# sd_debug.net
KiCad netlist of a schematic drawn in Altium Designer
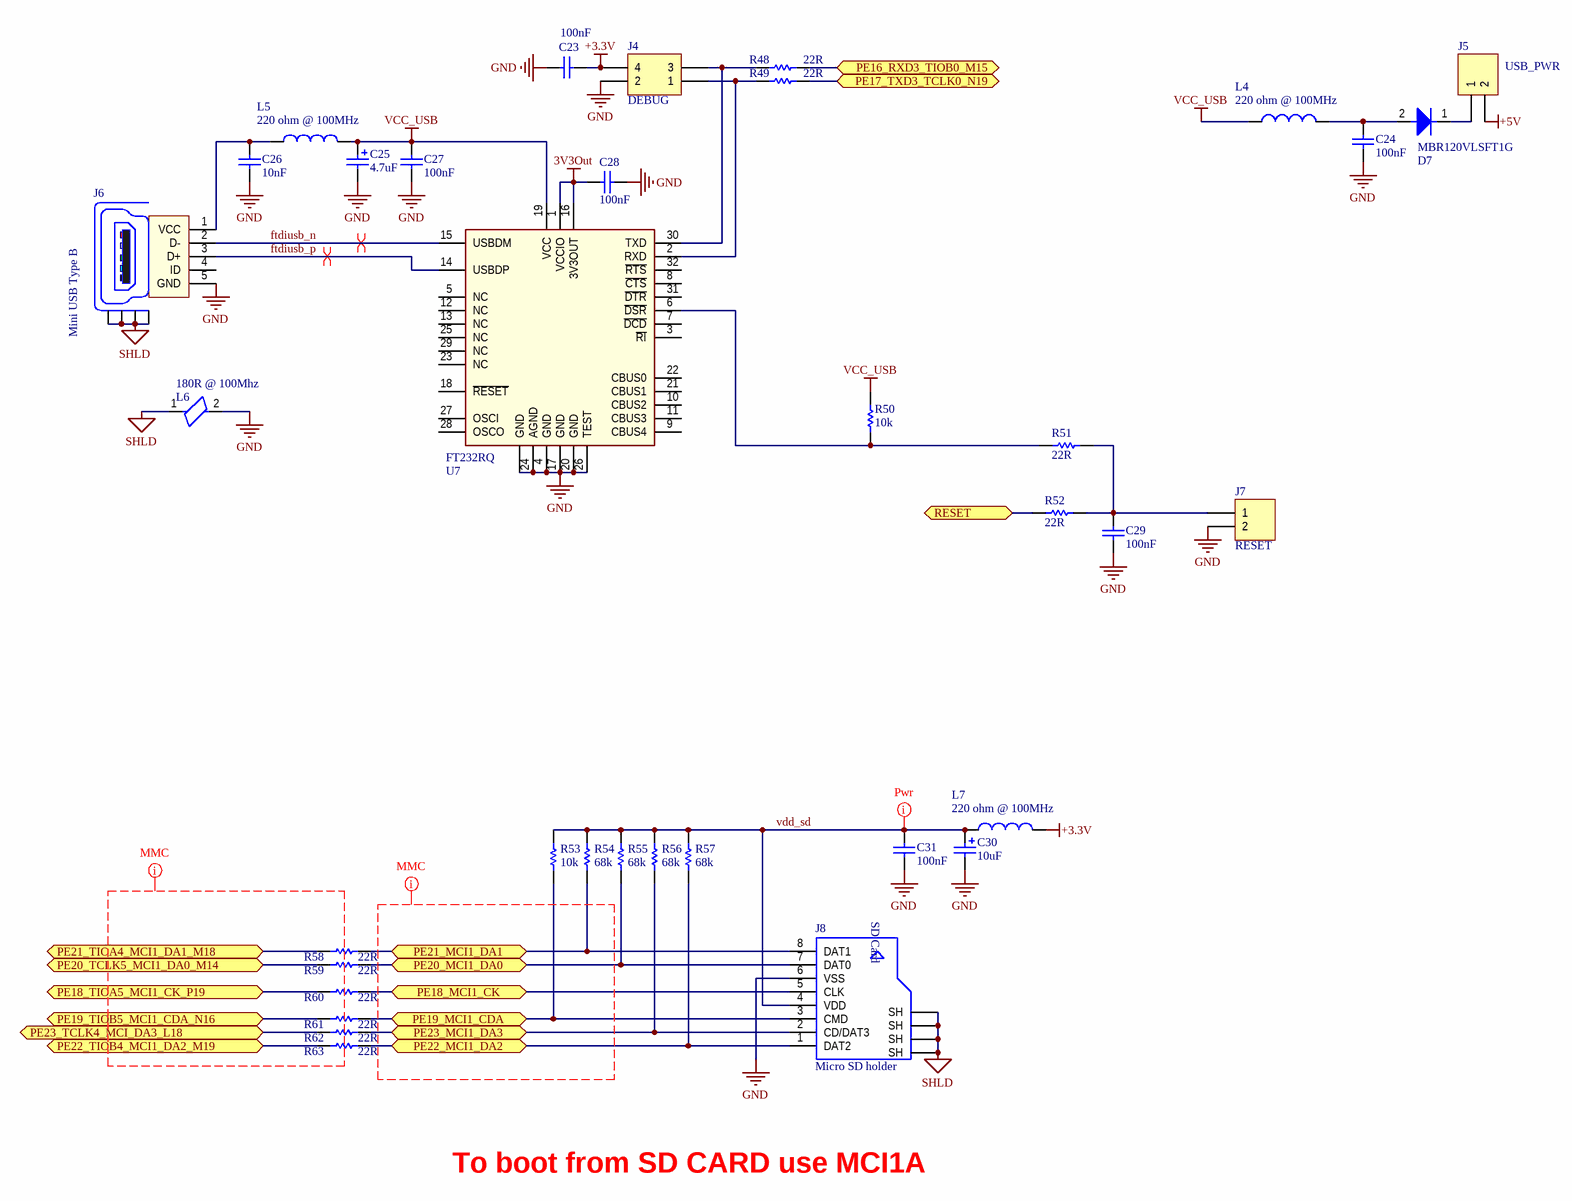
[diagram p0: sd_debug.SchDoc]

(export (version "E")
  (design (tool "Eeschema 10.0.6"))
  (components
    (comp (ref "C23")
      (value "100nF")
      (footprint "0603_[1608]")
      (description "Ceramic X7R 50V")
      (fields (field (name "PUBLISHER") "Altium Limited"))
      (libsource (lib "DEVELER_Library") (part "Cap"))
    )
    (comp (ref "C24")
      (value "100nF")
      (footprint "0603_[1608]")
      (description "Ceramic X7R 50V")
      (fields (field (name "PUBLISHER") "Altium Limited"))
      (libsource (lib "DEVELER_Library") (part "Cap"))
    )
    (comp (ref "C25")
      (value "4.7uF")
      (footprint "1206_[3216]")
      (description "Ceramic X5R 25V")
      (fields (field (name "PUBLISHER") "Altium Limited"))
      (libsource (lib "DEVELER_Library") (part "Cap Pol1"))
    )
    (comp (ref "C26")
      (value "10nF")
      (footprint "0603_[1608]")
      (description "Ceramic X7R 50V")
      (fields (field (name "PUBLISHER") "Altium Limited"))
      (libsource (lib "DEVELER_Library") (part "Cap"))
    )
    (comp (ref "C27")
      (value "100nF")
      (footprint "0603_[1608]")
      (description "Ceramic X7R 50V")
      (fields (field (name "PUBLISHER") "Altium Limited"))
      (libsource (lib "DEVELER_Library") (part "Cap"))
    )
    (comp (ref "C28")
      (value "100nF")
      (footprint "0603_[1608]")
      (description "Ceramic X7R 50V")
      (fields (field (name "PUBLISHER") "Altium Limited"))
      (libsource (lib "DEVELER_Library") (part "Cap"))
    )
    (comp (ref "C29")
      (value "100nF")
      (footprint "0603_[1608]")
      (description "Ceramic X7R 50V")
      (fields (field (name "PUBLISHER") "Altium Limited"))
      (libsource (lib "DEVELER_Library") (part "Cap"))
    )
    (comp (ref "C30")
      (value "10uF")
      (footprint "1206_[3216]")
      (description "Ceramic X5R 25V")
      (fields (field (name "PUBLISHER") "Altium Limited"))
      (libsource (lib "DEVELER_Library") (part "Cap Pol1"))
    )
    (comp (ref "C31")
      (value "100nF")
      (footprint "0603_[1608]")
      (description "Ceramic X7R 50V")
      (fields (field (name "PUBLISHER") "Altium Limited"))
      (libsource (lib "Miscellaneous Devices") (part "Cap"))
    )
    (comp (ref "D7")
      (value "MBR120VLSFT1G")
      (footprint "SOD-123")
      (description "Diode Schottky  low Vf, If 1A (PMEG3010ER; MBRX120LF)")
      (libsource (lib "DEVELER_Library") (part "Diode"))
    )
    (comp (ref "J4")
      (value "DEBUG")
      (footprint "HEADER_2X2_2.54MM_THD")
      (description "Pin Header, 4pin, 2x2, 2.54mm, THD")
      (fields (field (name "PUBLISHER") "Altium Limited"))
      (libsource (lib "Miscellaneous Connectors") (part "Header 2X2"))
    )
    (comp (ref "J5")
      (value "USB_PWR")
      (footprint "HEADER_1X2_2.54MM_THD")
      (description "Pin Header, 2pin, 1x2, 2.54mm, THD")
      (fields (field (name "PUBLISHER") "Altium Limited"))
      (libsource (lib "Miscellaneous Connectors") (part "Header 2"))
    )
    (comp (ref "J6")
      (value "Mini USB Type B")
      (footprint "usb_typeB_mini_smd")
      (description "Mini USB SMT Type B 5 Contacts (WE 65100516121)")
      (fields
        (field (name "MANUFACTURER") "Würth Elektronik eiSos GmbH")
        (field (name "PARTNO") "65100516121")
        (field (name "CREATED BY") "Karrer Zheng")
      )
      (libsource (lib "DEVELER_Library") (part "USB_Con_Type_B_mini_SMT"))
    )
    (comp (ref "J7")
      (value "RESET")
      (footprint "HEADER_1X2_2.54MM_THD")
      (description "Pin Header, 2pin, 1x2, 2.54mm, THD")
      (fields (field (name "PUBLISHER") "Altium Limited"))
      (libsource (lib "") (part "Header 2_1"))
    )
    (comp (ref "J8")
      (value "Micro SD holder")
      (footprint "micro_sd_holder_pp")
      (description "WR-CRD Micro SD_Push and Push (693071010811)")
      (fields
        (field (name "MANUFACTURER") "Würth Elektronik eiSos GmbH")
        (field (name "PARTNO") "693071010811")
        (field (name "CREATED BY") "Karrer Zheng")
      )
      (libsource (lib "DEVELER_Library") (part "micro_sd_holde"))
    )
    (comp (ref "L4")
      (value "220 ohm @ 100MHz")
      (footprint "0805_[2012]")
      (description "WE 742792022")
      (libsource (lib "DEVELER_Library") (part "Inductor"))
    )
    (comp (ref "L5")
      (value "220 ohm @ 100MHz")
      (footprint "0805_[2012]")
      (description "WE 742792022")
      (libsource (lib "DEVELER_Library") (part "Inductor"))
    )
    (comp (ref "L6")
      (value "180R @ 100Mhz")
      (footprint "0603_[1608]")
      (description "Ferrite Beat (WE 7427927218)")
      (libsource (lib "project42_lib") (part "BEAD_ FERRITE"))
    )
    (comp (ref "L7")
      (value "220 ohm @ 100MHz")
      (footprint "0805_[2012]")
      (description "WE 742792022")
      (libsource (lib "DEVELER_Library") (part "Inductor"))
    )
    (comp (ref "R48")
      (value "22R")
      (footprint "0603_[1608]")
      (description "Resistor")
      (fields (field (name "PUBLISHER") "Altium Limited"))
      (libsource (lib "DEVELER_Library") (part "Res1"))
    )
    (comp (ref "R49")
      (value "22R")
      (footprint "0603_[1608]")
      (description "Resistor")
      (fields (field (name "PUBLISHER") "Altium Limited"))
      (libsource (lib "DEVELER_Library") (part "Res1"))
    )
    (comp (ref "R50")
      (value "10k")
      (footprint "0603_[1608]")
      (description "Resistor")
      (fields (field (name "PUBLISHER") "Altium Limited"))
      (libsource (lib "DEVELER_Library") (part "Res1"))
    )
    (comp (ref "R51")
      (value "22R")
      (footprint "0603_[1608]")
      (description "Resistor")
      (fields (field (name "PUBLISHER") "Altium Limited"))
      (libsource (lib "DEVELER_Library") (part "Res1"))
    )
    (comp (ref "R52")
      (value "22R")
      (footprint "0603_[1608]")
      (description "Resistor")
      (fields (field (name "PUBLISHER") "Altium Limited"))
      (libsource (lib "DEVELER_Library") (part "Res1"))
    )
    (comp (ref "R53")
      (value "10k")
      (footprint "0603_[1608]")
      (description "Resistor")
      (fields (field (name "PUBLISHER") "Altium Limited"))
      (libsource (lib "DEVELER_Library") (part "Res1"))
    )
    (comp (ref "R54")
      (value "68k")
      (footprint "0603_[1608]")
      (description "Resistor")
      (fields (field (name "PUBLISHER") "Altium Limited"))
      (libsource (lib "DEVELER_Library") (part "Res1"))
    )
    (comp (ref "R55")
      (value "68k")
      (footprint "0603_[1608]")
      (description "Resistor")
      (fields (field (name "PUBLISHER") "Altium Limited"))
      (libsource (lib "DEVELER_Library") (part "Res1"))
    )
    (comp (ref "R56")
      (value "68k")
      (footprint "0603_[1608]")
      (description "Resistor")
      (fields (field (name "PUBLISHER") "Altium Limited"))
      (libsource (lib "DEVELER_Library") (part "Res1"))
    )
    (comp (ref "R57")
      (value "68k")
      (footprint "0603_[1608]")
      (description "Resistor")
      (fields (field (name "PUBLISHER") "Altium Limited"))
      (libsource (lib "DEVELER_Library") (part "Res1"))
    )
    (comp (ref "R58")
      (value "22R")
      (footprint "0603_[1608]")
      (description "Resistor")
      (fields (field (name "PUBLISHER") "Altium Limited"))
      (libsource (lib "DEVELER_Library") (part "Res1"))
    )
    (comp (ref "R59")
      (value "22R")
      (footprint "0603_[1608]")
      (description "Resistor")
      (fields (field (name "PUBLISHER") "Altium Limited"))
      (libsource (lib "DEVELER_Library") (part "Res1"))
    )
    (comp (ref "R60")
      (value "22R")
      (footprint "0603_[1608]")
      (description "Resistor")
      (fields (field (name "PUBLISHER") "Altium Limited"))
      (libsource (lib "DEVELER_Library") (part "Res1"))
    )
    (comp (ref "R61")
      (value "22R")
      (footprint "0603_[1608]")
      (description "Resistor")
      (fields (field (name "PUBLISHER") "Altium Limited"))
      (libsource (lib "DEVELER_Library") (part "Res1"))
    )
    (comp (ref "R62")
      (value "22R")
      (footprint "0603_[1608]")
      (description "Resistor")
      (fields (field (name "PUBLISHER") "Altium Limited"))
      (libsource (lib "DEVELER_Library") (part "Res1"))
    )
    (comp (ref "R63")
      (value "22R")
      (footprint "0603_[1608]")
      (description "Resistor")
      (fields (field (name "PUBLISHER") "Altium Limited"))
      (libsource (lib "DEVELER_Library") (part "Res1"))
    )
    (comp (ref "U7")
      (value "FT232RQ")
      (footprint "QFN-32")
      (description "Serial TTL 232 <-> USB (QFN-32)")
      (libsource (lib "DEVELER_Library") (part "FT232RQ"))
    )
  )
  (nets
    (net (code "1") (name "+3.3V") (class "Default")
      (node (ref "C23") (pin "1") (pinfunction "1_1") (pintype "passive"))
      (node (ref "J4") (pin "4") (pinfunction "4_4") (pintype "passive"))
      (node (ref "L7") (pin "1") (pinfunction "1_1") (pintype "passive"))
    )
    (net (code "2") (name "+5V") (class "Default")
      (node (ref "J5") (pin "2") (pinfunction "2_2") (pintype "passive"))
    )
    (net (code "3") (name "/PE16_RXD3_TIOB0_M15") (class "Default")
      (node (ref "R48") (pin "1") (pinfunction "1_1") (pintype "passive"))
    )
    (net (code "4") (name "/PE17_TXD3_TCLK0_N19") (class "Default")
      (node (ref "R49") (pin "1") (pinfunction "1_1") (pintype "passive"))
    )
    (net (code "5") (name "/PE18_MCI1_CK") (class "Default")
      (node (ref "J8") (pin "5") (pinfunction "CLK_5") (pintype "passive"))
      (node (ref "R60") (pin "2") (pinfunction "2_2") (pintype "passive"))
    )
    (net (code "6") (name "/PE18_TIOA5_MCI1_CK_P19") (class "Default")
      (node (ref "R60") (pin "1") (pinfunction "1_1") (pintype "passive"))
    )
    (net (code "7") (name "/PE19_MCI1_CDA") (class "Default")
      (node (ref "J8") (pin "3") (pinfunction "CMD_3") (pintype "passive"))
      (node (ref "R53") (pin "2") (pinfunction "2_2") (pintype "passive"))
      (node (ref "R61") (pin "2") (pinfunction "2_2") (pintype "passive"))
    )
    (net (code "8") (name "/PE19_TIOB5_MCI1_CDA_N16") (class "Default")
      (node (ref "R61") (pin "1") (pinfunction "1_1") (pintype "passive"))
    )
    (net (code "9") (name "/PE20_MCI1_DA0") (class "Default")
      (node (ref "J8") (pin "7") (pinfunction "DAT0_7") (pintype "passive"))
      (node (ref "R55") (pin "2") (pinfunction "2_2") (pintype "passive"))
      (node (ref "R59") (pin "2") (pinfunction "2_2") (pintype "passive"))
    )
    (net (code "10") (name "/PE20_TCLK5_MCI1_DA0_M14") (class "Default")
      (node (ref "R59") (pin "1") (pinfunction "1_1") (pintype "passive"))
    )
    (net (code "11") (name "/PE21_MCI1_DA1") (class "Default")
      (node (ref "J8") (pin "8") (pinfunction "DAT1_8") (pintype "passive"))
      (node (ref "R54") (pin "2") (pinfunction "2_2") (pintype "passive"))
      (node (ref "R58") (pin "2") (pinfunction "2_2") (pintype "passive"))
    )
    (net (code "12") (name "/PE21_TIOA4_MCI1_DA1_M18") (class "Default")
      (node (ref "R58") (pin "1") (pinfunction "1_1") (pintype "passive"))
    )
    (net (code "13") (name "/PE22_MCI1_DA2") (class "Default")
      (node (ref "J8") (pin "1") (pinfunction "DAT2_1") (pintype "passive"))
      (node (ref "R57") (pin "2") (pinfunction "2_2") (pintype "passive"))
      (node (ref "R63") (pin "2") (pinfunction "2_2") (pintype "passive"))
    )
    (net (code "14") (name "/PE22_TIOB4_MCI1_DA2_M19") (class "Default")
      (node (ref "R63") (pin "1") (pinfunction "1_1") (pintype "passive"))
    )
    (net (code "15") (name "/PE23_MCI1_DA3") (class "Default")
      (node (ref "J8") (pin "2") (pinfunction "CD/DAT3_2") (pintype "passive"))
      (node (ref "R56") (pin "2") (pinfunction "2_2") (pintype "passive"))
      (node (ref "R62") (pin "2") (pinfunction "2_2") (pintype "passive"))
    )
    (net (code "16") (name "/PE23_TCLK4_MCI_DA3_L18") (class "Default")
      (node (ref "R62") (pin "1") (pinfunction "1_1") (pintype "passive"))
    )
    (net (code "17") (name "/RESET") (class "Default")
      (node (ref "R52") (pin "2") (pinfunction "2_2") (pintype "passive"))
    )
    (net (code "18") (name "/ftdiusb_n") (class "Default")
      (node (ref "J6") (pin "2") (pinfunction "D-_2") (pintype "passive"))
      (node (ref "U7") (pin "15") (pinfunction "USBDM_15") (pintype "passive"))
    )
    (net (code "19") (name "/ftdiusb_p") (class "Default")
      (node (ref "J6") (pin "3") (pinfunction "D+_3") (pintype "passive"))
      (node (ref "U7") (pin "14") (pinfunction "USBDP_14") (pintype "passive"))
    )
    (net (code "20") (name "/vdd_sd") (class "Default")
      (node (ref "C30") (pin "1") (pinfunction "1_1") (pintype "passive"))
      (node (ref "C31") (pin "1") (pinfunction "1_1") (pintype "passive"))
      (node (ref "J8") (pin "4") (pinfunction "VDD_4") (pintype "passive"))
      (node (ref "L7") (pin "2") (pinfunction "2_2") (pintype "passive"))
      (node (ref "R53") (pin "1") (pinfunction "1_1") (pintype "passive"))
      (node (ref "R54") (pin "1") (pinfunction "1_1") (pintype "passive"))
      (node (ref "R55") (pin "1") (pinfunction "1_1") (pintype "passive"))
      (node (ref "R56") (pin "1") (pinfunction "1_1") (pintype "passive"))
      (node (ref "R57") (pin "1") (pinfunction "1_1") (pintype "passive"))
    )
    (net (code "21") (name "3V3Out") (class "Default")
      (node (ref "C28") (pin "1") (pinfunction "1_1") (pintype "passive"))
      (node (ref "U7") (pin "1") (pinfunction "VCCIO_1") (pintype "passive"))
      (node (ref "U7") (pin "16") (pinfunction "3V3OUT_16") (pintype "passive"))
    )
    (net (code "22") (name "GND") (class "Default")
      (node (ref "C23") (pin "2") (pinfunction "2_2") (pintype "passive"))
      (node (ref "C24") (pin "1") (pinfunction "1_1") (pintype "passive"))
      (node (ref "C25") (pin "2") (pinfunction "2_2") (pintype "passive"))
      (node (ref "C26") (pin "2") (pinfunction "2_2") (pintype "passive"))
      (node (ref "C27") (pin "2") (pinfunction "2_2") (pintype "passive"))
      (node (ref "C28") (pin "2") (pinfunction "2_2") (pintype "passive"))
      (node (ref "C29") (pin "1") (pinfunction "1_1") (pintype "passive"))
      (node (ref "C30") (pin "2") (pinfunction "2_2") (pintype "passive"))
      (node (ref "C31") (pin "2") (pinfunction "2_2") (pintype "passive"))
      (node (ref "J4") (pin "2") (pinfunction "2_2") (pintype "passive"))
      (node (ref "J6") (pin "5") (pinfunction "GND_5") (pintype "passive"))
      (node (ref "J7") (pin "2") (pinfunction "2_2") (pintype "passive"))
      (node (ref "J8") (pin "6") (pinfunction "VSS_6") (pintype "passive"))
      (node (ref "L6") (pin "2") (pinfunction "2_2") (pintype "passive"))
      (node (ref "U7") (pin "17") (pinfunction "GND_17") (pintype "passive"))
      (node (ref "U7") (pin "20") (pinfunction "GND_20") (pintype "passive"))
      (node (ref "U7") (pin "24") (pinfunction "AGND_24") (pintype "passive"))
      (node (ref "U7") (pin "26") (pinfunction "TEST_26") (pintype "passive"))
      (node (ref "U7") (pin "4") (pinfunction "GND_4") (pintype "passive"))
      (node (ref "U7") (pin "GND_PAD") (pinfunction "GND_GND_PAD") (pintype "passive"))
    )
    (net (code "23") (name "Net-(C29-Pad2)") (class "Default")
      (node (ref "C29") (pin "2") (pinfunction "2_2") (pintype "passive"))
      (node (ref "J7") (pin "1") (pinfunction "1_1") (pintype "passive"))
      (node (ref "R51") (pin "1") (pinfunction "1_1") (pintype "passive"))
      (node (ref "R52") (pin "1") (pinfunction "1_1") (pintype "passive"))
    )
    (net (code "24") (name "Net-(D7-A)") (class "Default")
      (node (ref "C24") (pin "2") (pinfunction "2_2") (pintype "passive"))
      (node (ref "D7") (pin "2") (pinfunction "A_2") (pintype "passive"))
      (node (ref "L4") (pin "1") (pinfunction "1_1") (pintype "passive"))
    )
    (net (code "25") (name "Net-(D7-K)") (class "Default")
      (node (ref "D7") (pin "1") (pinfunction "K_1") (pintype "passive"))
      (node (ref "J5") (pin "1") (pinfunction "1_1") (pintype "passive"))
    )
    (net (code "26") (name "Net-(J6-VCC)") (class "Default")
      (node (ref "C26") (pin "1") (pinfunction "1_1") (pintype "passive"))
      (node (ref "J6") (pin "1") (pinfunction "VCC_1") (pintype "passive"))
      (node (ref "L5") (pin "2") (pinfunction "2_2") (pintype "passive"))
    )
    (net (code "27") (name "Net-(U7-RXD)") (class "Default")
      (node (ref "J4") (pin "1") (pinfunction "1_1") (pintype "passive"))
      (node (ref "R49") (pin "2") (pinfunction "2_2") (pintype "passive"))
      (node (ref "U7") (pin "2") (pinfunction "RXD_2") (pintype "passive"))
    )
    (net (code "28") (name "Net-(U7-TXD)") (class "Default")
      (node (ref "J4") (pin "3") (pinfunction "3_3") (pintype "passive"))
      (node (ref "R48") (pin "2") (pinfunction "2_2") (pintype "passive"))
      (node (ref "U7") (pin "30") (pinfunction "TXD_30") (pintype "passive"))
    )
    (net (code "29") (name "Net-(U7-~{DSR})") (class "Default")
      (node (ref "R50") (pin "2") (pinfunction "2_2") (pintype "passive"))
      (node (ref "R51") (pin "2") (pinfunction "2_2") (pintype "passive"))
      (node (ref "U7") (pin "6") (pinfunction "~{DSR}_6") (pintype "passive"))
    )
    (net (code "30") (name "SHLD") (class "Default")
      (node (ref "J6") (pin "Z1") (pinfunction "Shield_Z1") (pintype "passive"))
      (node (ref "J6") (pin "Z2") (pinfunction "Shield_Z2") (pintype "passive"))
      (node (ref "J6") (pin "Z3") (pinfunction "Shield_Z3") (pintype "passive"))
      (node (ref "J6") (pin "Z4") (pinfunction "Shield_Z4") (pintype "passive"))
      (node (ref "J8") (pin "Z1") (pinfunction "SH_Z1") (pintype "passive"))
      (node (ref "J8") (pin "Z2") (pinfunction "SH_Z2") (pintype "passive"))
      (node (ref "J8") (pin "Z3") (pinfunction "SH_Z3") (pintype "passive"))
      (node (ref "J8") (pin "Z4") (pinfunction "SH_Z4") (pintype "passive"))
      (node (ref "L6") (pin "1") (pinfunction "1_1") (pintype "passive"))
    )
    (net (code "31") (name "VCC_USB") (class "Default")
      (node (ref "C25") (pin "1") (pinfunction "1_1") (pintype "passive"))
      (node (ref "C27") (pin "1") (pinfunction "1_1") (pintype "passive"))
      (node (ref "L4") (pin "2") (pinfunction "2_2") (pintype "passive"))
      (node (ref "L5") (pin "1") (pinfunction "1_1") (pintype "passive"))
      (node (ref "R50") (pin "1") (pinfunction "1_1") (pintype "passive"))
      (node (ref "U7") (pin "19") (pinfunction "VCC_19") (pintype "passive"))
    )
    (net (code "32") (name "unconnected-(J6-ID-Pad4)") (class "Default")
      (node (ref "J6") (pin "4") (pinfunction "ID_4") (pintype "passive"))
    )
    (net (code "33") (name "unconnected-(U7-CBUS0-Pad22)") (class "Default")
      (node (ref "U7") (pin "22") (pinfunction "CBUS0_22") (pintype "passive"))
    )
    (net (code "34") (name "unconnected-(U7-CBUS1-Pad21)") (class "Default")
      (node (ref "U7") (pin "21") (pinfunction "CBUS1_21") (pintype "passive"))
    )
    (net (code "35") (name "unconnected-(U7-CBUS2-Pad10)") (class "Default")
      (node (ref "U7") (pin "10") (pinfunction "CBUS2_10") (pintype "passive"))
    )
    (net (code "36") (name "unconnected-(U7-CBUS3-Pad11)") (class "Default")
      (node (ref "U7") (pin "11") (pinfunction "CBUS3_11") (pintype "passive"))
    )
    (net (code "37") (name "unconnected-(U7-CBUS4-Pad9)") (class "Default")
      (node (ref "U7") (pin "9") (pinfunction "CBUS4_9") (pintype "passive"))
    )
    (net (code "38") (name "unconnected-(U7-NC-Pad5)") (class "Default")
      (node (ref "U7") (pin "5") (pinfunction "NC_5") (pintype "passive"))
    )
    (net (code "39") (name "unconnected-(U7-NC-Pad12)") (class "Default")
      (node (ref "U7") (pin "12") (pinfunction "NC_12") (pintype "passive"))
    )
    (net (code "40") (name "unconnected-(U7-NC-Pad13)") (class "Default")
      (node (ref "U7") (pin "13") (pinfunction "NC_13") (pintype "passive"))
    )
    (net (code "41") (name "unconnected-(U7-NC-Pad23)") (class "Default")
      (node (ref "U7") (pin "23") (pinfunction "NC_23") (pintype "passive"))
    )
    (net (code "42") (name "unconnected-(U7-NC-Pad25)") (class "Default")
      (node (ref "U7") (pin "25") (pinfunction "NC_25") (pintype "passive"))
    )
    (net (code "43") (name "unconnected-(U7-NC-Pad29)") (class "Default")
      (node (ref "U7") (pin "29") (pinfunction "NC_29") (pintype "passive"))
    )
    (net (code "44") (name "unconnected-(U7-OSCI-Pad27)") (class "Default")
      (node (ref "U7") (pin "27") (pinfunction "OSCI_27") (pintype "passive"))
    )
    (net (code "45") (name "unconnected-(U7-OSCO-Pad28)") (class "Default")
      (node (ref "U7") (pin "28") (pinfunction "OSCO_28") (pintype "passive"))
    )
    (net (code "46") (name "unconnected-(U7-~{CTS}-Pad8)") (class "Default")
      (node (ref "U7") (pin "8") (pinfunction "~{CTS}_8") (pintype "passive"))
    )
    (net (code "47") (name "unconnected-(U7-~{DCD}-Pad7)") (class "Default")
      (node (ref "U7") (pin "7") (pinfunction "~{DCD}_7") (pintype "passive"))
    )
    (net (code "48") (name "unconnected-(U7-~{DTR}-Pad31)") (class "Default")
      (node (ref "U7") (pin "31") (pinfunction "~{DTR}_31") (pintype "passive"))
    )
    (net (code "49") (name "unconnected-(U7-~{RESET}-Pad18)") (class "Default")
      (node (ref "U7") (pin "18") (pinfunction "~{RESET}_18") (pintype "passive"))
    )
    (net (code "50") (name "unconnected-(U7-~{RI}-Pad3)") (class "Default")
      (node (ref "U7") (pin "3") (pinfunction "~{RI}_3") (pintype "passive"))
    )
    (net (code "51") (name "unconnected-(U7-~{RTS}-Pad32)") (class "Default")
      (node (ref "U7") (pin "32") (pinfunction "~{RTS}_32") (pintype "passive"))
    )
  )
)
